# serial.net
KiCad netlist of a schematic drawn in Altium Designer
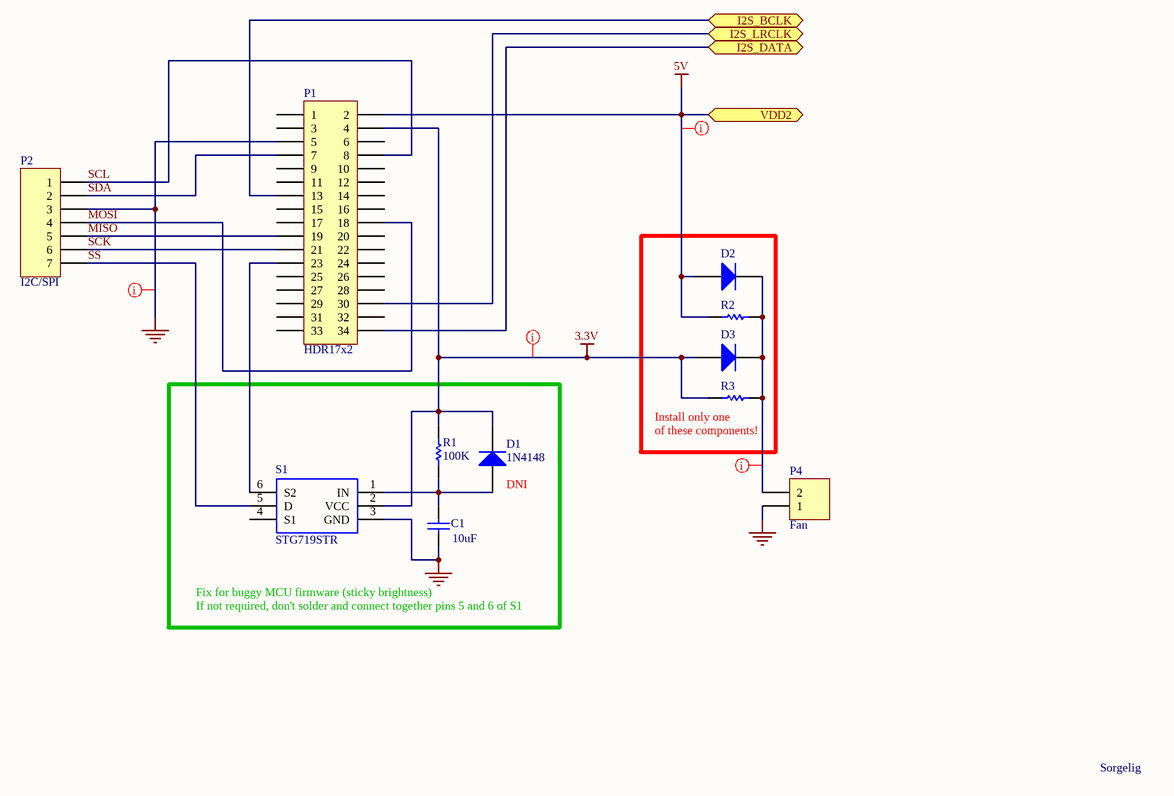
[diagram p0: serial.SchDoc]

(export (version "E")
  (design (tool "Eeschema 10.0.6"))
  (components
    (comp (ref "C1")
      (value "10uF")
      (footprint "C0805")
      (description "Ceramic Chip Capacitor - Standard")
      (fields (field (name "Comment") "C0805") (field (name "PUBLISHER") "Altium Limited"))
      (libsource (lib "KEMET Chip Capacitor") (part "C0805"))
    )
    (comp (ref "D1")
      (value "1N4148")
      (footprint "DIODE")
      (description "Default Diode")
      (fields (field (name "PUBLISHER") "Altium Limited"))
      (libsource (lib "Miscellaneous Devices") (part "Diode"))
    )
    (comp (ref "D2")
      (value "Diode")
      (description "Default Diode")
      (fields (field (name "PUBLISHER") "Altium Limited"))
      (libsource (lib "Miscellaneous Devices") (part "Diode"))
    )
    (comp (ref "D3")
      (value "Diode")
      (description "Default Diode")
      (fields (field (name "PUBLISHER") "Altium Limited"))
      (libsource (lib "Miscellaneous Devices") (part "Diode"))
    )
    (comp (ref "P1") (value "HDR17x2") (footprint "HDR17X2_90") (libsource (lib "lib") (part "HDR17x2")))
    (comp (ref "P2")
      (value "I2C/SPI")
      (footprint "HDR1X7")
      (description "Header, 7-Pin")
      (fields (field (name "PUBLISHER") "Altium Limited"))
      (libsource (lib "Miscellaneous Connectors") (part "Header 7"))
    )
    (comp (ref "P4")
      (value "Fan")
      (footprint "HDR1X2")
      (description "Header, 2-Pin")
      (fields (field (name "PUBLISHER") "Altium Limited"))
      (libsource (lib "Miscellaneous Connectors") (part "Header 2"))
    )
    (comp (ref "R1")
      (value "100K")
      (footprint "R0805")
      (fields (field (name "PUBLISHER") "Altium Limited"))
      (libsource (lib "Panasonic Resistor") (part "ERJ6RS"))
    )
    (comp (ref "R2")
      (value "10")
      (footprint "6-0805")
      (fields (field (name "PUBLISHER") "Altium Limited"))
      (libsource (lib "Panasonic Resistor") (part "ERJ6RS"))
    )
    (comp (ref "R3")
      (value "10")
      (footprint "6-0805")
      (fields (field (name "PUBLISHER") "Altium Limited"))
      (libsource (lib "Panasonic Resistor") (part "ERJ6RS"))
    )
    (comp (ref "S1")
      (value "STG719STR")
      (footprint "SOT23-6_L")
      (description "STMICROELECTRONICS - STG719STR - IC, SWITCH, SPDT, SMD")
      (libsource (lib "lib") (part "STG719STR"))
    )
  )
  (nets
    (net (code "1") (name "/I2S_BCLK") (class "Default")
      (node (ref "P1") (pin "13") (pinfunction "13_13") (pintype "passive"))
    )
    (net (code "2") (name "/I2S_DATA") (class "Default")
      (node (ref "P1") (pin "34") (pinfunction "34_34") (pintype "passive"))
    )
    (net (code "3") (name "/I2S_LRCLK") (class "Default")
      (node (ref "P1") (pin "30") (pinfunction "30_30") (pintype "passive"))
    )
    (net (code "4") (name "/MISO") (class "Default")
      (node (ref "P1") (pin "19") (pinfunction "19_19") (pintype "passive"))
      (node (ref "P2") (pin "5") (pinfunction "5_5") (pintype "passive"))
    )
    (net (code "5") (name "/MOSI") (class "Default")
      (node (ref "P1") (pin "18") (pinfunction "18_18") (pintype "passive"))
      (node (ref "P2") (pin "4") (pinfunction "4_4") (pintype "passive"))
    )
    (net (code "6") (name "/SCK") (class "Default")
      (node (ref "P1") (pin "21") (pinfunction "21_21") (pintype "passive"))
      (node (ref "P2") (pin "6") (pinfunction "6_6") (pintype "passive"))
    )
    (net (code "7") (name "/SCL") (class "Default")
      (node (ref "P1") (pin "8") (pinfunction "8_8") (pintype "passive"))
      (node (ref "P2") (pin "1") (pinfunction "1_1") (pintype "passive"))
    )
    (net (code "8") (name "/SDA") (class "Default")
      (node (ref "P1") (pin "7") (pinfunction "7_7") (pintype "passive"))
      (node (ref "P2") (pin "2") (pinfunction "2_2") (pintype "passive"))
    )
    (net (code "9") (name "/SS") (class "Default")
      (node (ref "P2") (pin "7") (pinfunction "7_7") (pintype "passive"))
      (node (ref "S1") (pin "5") (pinfunction "D_5") (pintype "passive"))
    )
    (net (code "10") (name "3.3V") (class "Default")
      (node (ref "D1") (pin "2") (pinfunction "K_2") (pintype "passive"))
      (node (ref "D3") (pin "1") (pinfunction "A_1") (pintype "passive"))
      (node (ref "P1") (pin "4") (pinfunction "4_4") (pintype "passive"))
      (node (ref "R1") (pin "2") (pinfunction "2_2") (pintype "passive"))
      (node (ref "R3") (pin "1") (pinfunction "1_1") (pintype "passive"))
      (node (ref "S1") (pin "2") (pinfunction "VCC_2") (pintype "passive"))
    )
    (net (code "11") (name "5V") (class "Default")
      (node (ref "D2") (pin "1") (pinfunction "A_1") (pintype "passive"))
      (node (ref "P1") (pin "2") (pinfunction "2_2") (pintype "passive"))
      (node (ref "R2") (pin "1") (pinfunction "1_1") (pintype "passive"))
    )
    (net (code "12") (name "GND") (class "Default")
      (node (ref "C1") (pin "1") (pinfunction "1_1") (pintype "passive"))
      (node (ref "P1") (pin "5") (pinfunction "5_5") (pintype "passive"))
      (node (ref "P2") (pin "3") (pinfunction "3_3") (pintype "passive"))
      (node (ref "P4") (pin "1") (pinfunction "1_1") (pintype "passive"))
      (node (ref "S1") (pin "3") (pinfunction "GND_3") (pintype "passive"))
    )
    (net (code "13") (name "Net-(D1-A)") (class "Default")
      (node (ref "C1") (pin "2") (pinfunction "2_2") (pintype "passive"))
      (node (ref "D1") (pin "1") (pinfunction "A_1") (pintype "passive"))
      (node (ref "R1") (pin "1") (pinfunction "1_1") (pintype "passive"))
      (node (ref "S1") (pin "1") (pinfunction "IN_1") (pintype "passive"))
    )
    (net (code "14") (name "Net-(D2-K)") (class "Default")
      (node (ref "D2") (pin "2") (pinfunction "K_2") (pintype "passive"))
      (node (ref "D3") (pin "2") (pinfunction "K_2") (pintype "passive"))
      (node (ref "P4") (pin "2") (pinfunction "2_2") (pintype "passive"))
      (node (ref "R2") (pin "2") (pinfunction "2_2") (pintype "passive"))
      (node (ref "R3") (pin "2") (pinfunction "2_2") (pintype "passive"))
    )
    (net (code "15") (name "Net-(S1-S2)") (class "Default")
      (node (ref "P1") (pin "23") (pinfunction "23_23") (pintype "passive"))
      (node (ref "S1") (pin "6") (pinfunction "S2_6") (pintype "passive"))
    )
    (net (code "16") (name "unconnected-(P1-Pad1)") (class "Default")
      (node (ref "P1") (pin "1") (pinfunction "1_1") (pintype "passive"))
    )
    (net (code "17") (name "unconnected-(P1-Pad3)") (class "Default")
      (node (ref "P1") (pin "3") (pinfunction "3_3") (pintype "passive"))
    )
    (net (code "18") (name "unconnected-(P1-Pad6)") (class "Default")
      (node (ref "P1") (pin "6") (pinfunction "6_6") (pintype "passive"))
    )
    (net (code "19") (name "unconnected-(P1-Pad9)") (class "Default")
      (node (ref "P1") (pin "9") (pinfunction "9_9") (pintype "passive"))
    )
    (net (code "20") (name "unconnected-(P1-Pad10)") (class "Default")
      (node (ref "P1") (pin "10") (pinfunction "10_10") (pintype "passive"))
    )
    (net (code "21") (name "unconnected-(P1-Pad11)") (class "Default")
      (node (ref "P1") (pin "11") (pinfunction "11_11") (pintype "passive"))
    )
    (net (code "22") (name "unconnected-(P1-Pad12)") (class "Default")
      (node (ref "P1") (pin "12") (pinfunction "12_12") (pintype "passive"))
    )
    (net (code "23") (name "unconnected-(P1-Pad14)") (class "Default")
      (node (ref "P1") (pin "14") (pinfunction "14_14") (pintype "passive"))
    )
    (net (code "24") (name "unconnected-(P1-Pad15)") (class "Default")
      (node (ref "P1") (pin "15") (pinfunction "15_15") (pintype "passive"))
    )
    (net (code "25") (name "unconnected-(P1-Pad16)") (class "Default")
      (node (ref "P1") (pin "16") (pinfunction "16_16") (pintype "passive"))
    )
    (net (code "26") (name "unconnected-(P1-Pad17)") (class "Default")
      (node (ref "P1") (pin "17") (pinfunction "17_17") (pintype "passive"))
    )
    (net (code "27") (name "unconnected-(P1-Pad20)") (class "Default")
      (node (ref "P1") (pin "20") (pinfunction "20_20") (pintype "passive"))
    )
    (net (code "28") (name "unconnected-(P1-Pad22)") (class "Default")
      (node (ref "P1") (pin "22") (pinfunction "22_22") (pintype "passive"))
    )
    (net (code "29") (name "unconnected-(P1-Pad24)") (class "Default")
      (node (ref "P1") (pin "24") (pinfunction "24_24") (pintype "passive"))
    )
    (net (code "30") (name "unconnected-(P1-Pad25)") (class "Default")
      (node (ref "P1") (pin "25") (pinfunction "25_25") (pintype "passive"))
    )
    (net (code "31") (name "unconnected-(P1-Pad26)") (class "Default")
      (node (ref "P1") (pin "26") (pinfunction "26_26") (pintype "passive"))
    )
    (net (code "32") (name "unconnected-(P1-Pad27)") (class "Default")
      (node (ref "P1") (pin "27") (pinfunction "27_27") (pintype "passive"))
    )
    (net (code "33") (name "unconnected-(P1-Pad28)") (class "Default")
      (node (ref "P1") (pin "28") (pinfunction "28_28") (pintype "passive"))
    )
    (net (code "34") (name "unconnected-(P1-Pad29)") (class "Default")
      (node (ref "P1") (pin "29") (pinfunction "29_29") (pintype "passive"))
    )
    (net (code "35") (name "unconnected-(P1-Pad31)") (class "Default")
      (node (ref "P1") (pin "31") (pinfunction "31_31") (pintype "passive"))
    )
    (net (code "36") (name "unconnected-(P1-Pad32)") (class "Default")
      (node (ref "P1") (pin "32") (pinfunction "32_32") (pintype "passive"))
    )
    (net (code "37") (name "unconnected-(P1-Pad33)") (class "Default")
      (node (ref "P1") (pin "33") (pinfunction "33_33") (pintype "passive"))
    )
    (net (code "38") (name "unconnected-(S1-S1-Pad4)") (class "Default")
      (node (ref "S1") (pin "4") (pinfunction "S1_4") (pintype "passive"))
    )
  )
)
